# Jlink-OB.net
KiCad netlist of a schematic drawn in Altium Designer
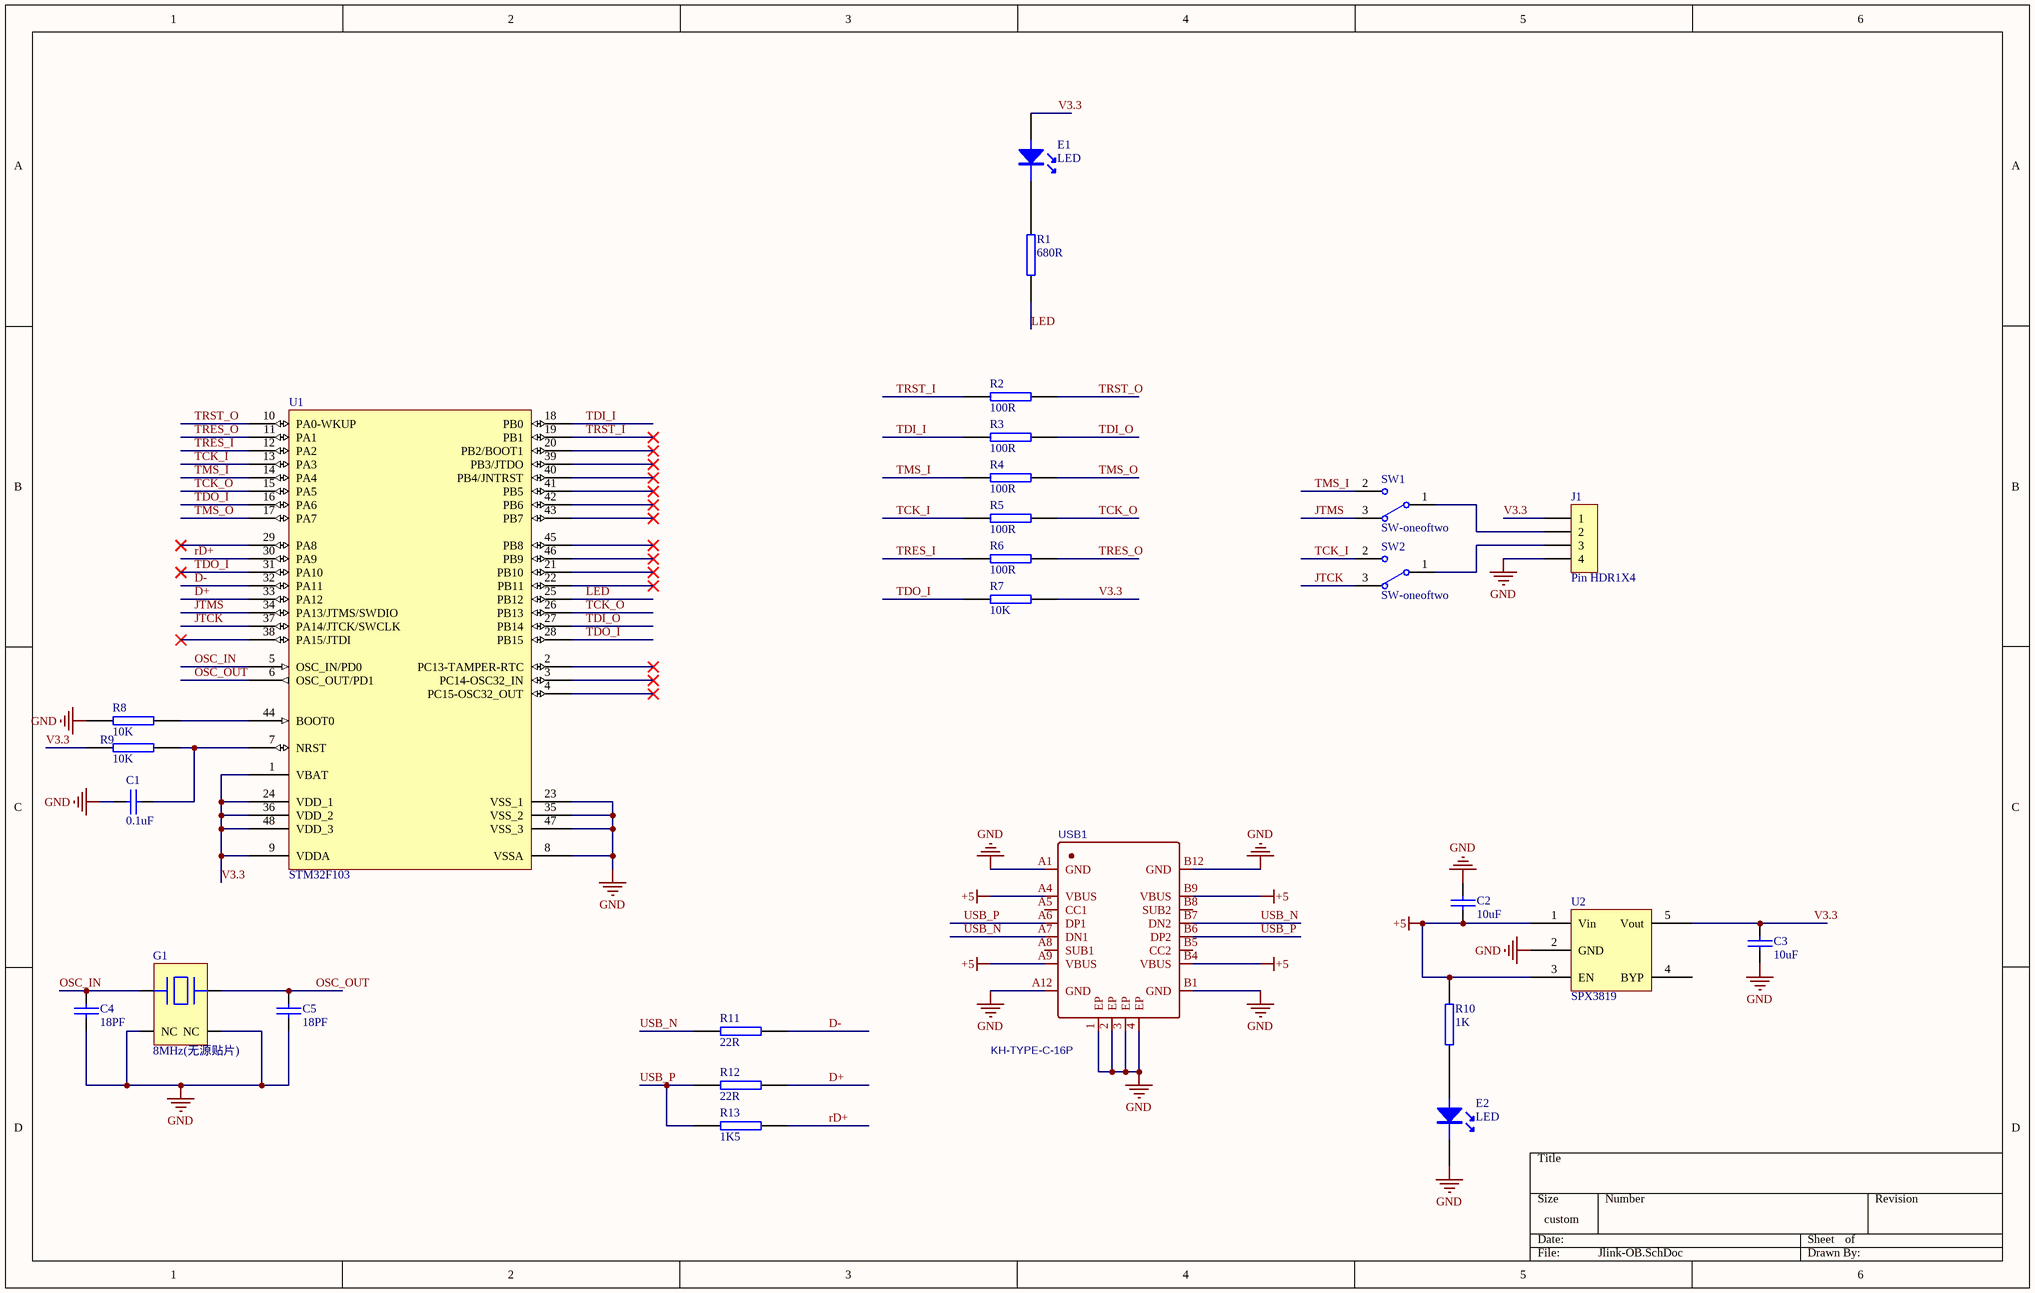
[diagram p0: Jlink-OB.SchDoc]

(export (version "E")
  (design (tool "Eeschema 10.0.6"))
  (components
    (comp (ref "C1")
      (value "0.1uF")
      (footprint "0603")
      (description "无极电容")
      (libsource (lib "chenjd") (part "CAP Nonpolarity"))
    )
    (comp (ref "C2")
      (value "10uF")
      (footprint "0603")
      (description "无极电容")
      (libsource (lib "chenjd") (part "CAP Nonpolarity"))
    )
    (comp (ref "C3")
      (value "10uF")
      (footprint "0603")
      (description "无极电容")
      (libsource (lib "chenjd") (part "CAP Nonpolarity"))
    )
    (comp (ref "C4")
      (value "18PF")
      (footprint "0603")
      (description "无极电容")
      (libsource (lib "chenjd") (part "CAP Nonpolarity"))
    )
    (comp (ref "C5")
      (value "18PF")
      (footprint "0603")
      (description "无极电容")
      (libsource (lib "chenjd") (part "CAP Nonpolarity"))
    )
    (comp (ref "E1")
      (value "LED")
      (footprint "LED_0603L")
      (description "LED灯")
      (libsource (lib "chenjd") (part "LED"))
    )
    (comp (ref "E2")
      (value "LED")
      (footprint "LED_0603L")
      (description "LED灯")
      (libsource (lib "chenjd") (part "LED"))
    )
    (comp (ref "G1")
      (value "8MHz(无源贴片)")
      (footprint "G3225")
      (description "无源晶振MCU使用")
      (libsource (lib "chenjd") (part "MM-11B"))
    )
    (comp (ref "J1")
      (value "Pin HDR1X4")
      (footprint "Pin HDR1X4/2.54mm-S")
      (libsource (lib "排针") (part "Pin HDR1X4"))
    )
    (comp (ref "R1")
      (value "680R")
      (footprint "0603")
      (description "电阻")
      (libsource (lib "chenjd") (part "R"))
    )
    (comp (ref "R2")
      (value "100R")
      (footprint "0603")
      (description "电阻")
      (libsource (lib "chenjd") (part "R"))
    )
    (comp (ref "R3")
      (value "100R")
      (footprint "0603")
      (description "电阻")
      (libsource (lib "chenjd") (part "R"))
    )
    (comp (ref "R4")
      (value "100R")
      (footprint "0603")
      (description "电阻")
      (libsource (lib "chenjd") (part "R"))
    )
    (comp (ref "R5")
      (value "100R")
      (footprint "0603")
      (description "电阻")
      (libsource (lib "chenjd") (part "R"))
    )
    (comp (ref "R6")
      (value "100R")
      (footprint "0603")
      (description "电阻")
      (libsource (lib "chenjd") (part "R"))
    )
    (comp (ref "R7")
      (value "10K")
      (footprint "0603")
      (description "电阻")
      (libsource (lib "chenjd") (part "R"))
    )
    (comp (ref "R8")
      (value "10K")
      (footprint "0603")
      (description "电阻")
      (libsource (lib "chenjd") (part "R"))
    )
    (comp (ref "R9")
      (value "10K")
      (footprint "0603")
      (description "电阻")
      (libsource (lib "chenjd") (part "R"))
    )
    (comp (ref "R10")
      (value "1K")
      (footprint "0603")
      (description "电阻")
      (libsource (lib "chenjd") (part "R"))
    )
    (comp (ref "R11")
      (value "22R")
      (footprint "0603")
      (description "电阻")
      (libsource (lib "chenjd") (part "R"))
    )
    (comp (ref "R12")
      (value "22R")
      (footprint "0603")
      (description "电阻")
      (libsource (lib "chenjd") (part "R"))
    )
    (comp (ref "R13")
      (value "1K5")
      (footprint "0603")
      (description "电阻")
      (libsource (lib "chenjd") (part "R"))
    )
    (comp (ref "SW1")
      (value "SW-oneoftwo")
      (footprint "SW-oneoftwo-0603")
      (description "二选一电阻开关")
      (libsource (lib "chenjd") (part "SW-oneoftwo"))
    )
    (comp (ref "SW2")
      (value "SW-oneoftwo")
      (footprint "SW-oneoftwo-0603")
      (description "二选一电阻开关")
      (libsource (lib "chenjd") (part "SW-oneoftwo"))
    )
    (comp (ref "U1")
      (value "STM32F103")
      (footprint "LQFP-48")
      (description "STM32F103C8T6")
      (fields (field (name "PUBLISHER") "Altium Limited"))
      (libsource (lib "chenjd") (part "STM32F103"))
    )
    (comp (ref "U2")
      (value "SPX3819")
      (footprint "SOT-23-5")
      (description "稳压器")
      (libsource (lib "chenjd") (part "SPX3819"))
    )
    (comp (ref "USB1")
      (value "KH-TYPE-C-16P")
      (footprint "USB-C-16P")
      (fields (field (name "BOM_SUPPLIER PART") "C709357") (field (name "CONTRIBUTOR") "LCSC"))
      (libsource (lib "chenjd") (part "USB-TYPE-C 16P"))
    )
  )
  (nets
    (net (code "1") (name "+5") (class "Default")
      (node (ref "C2") (pin "2") (pinfunction "2_2") (pintype "passive"))
      (node (ref "R10") (pin "1") (pinfunction "1_1") (pintype "passive"))
      (node (ref "U2") (pin "1") (pinfunction "Vin_1") (pintype "passive"))
      (node (ref "U2") (pin "3") (pinfunction "EN_3") (pintype "passive"))
      (node (ref "USB1") (pin "A4") (pinfunction "VBUS_A4") (pintype "passive"))
      (node (ref "USB1") (pin "A9") (pinfunction "VBUS_A9") (pintype "passive"))
      (node (ref "USB1") (pin "B4") (pinfunction "VBUS_B4") (pintype "passive"))
      (node (ref "USB1") (pin "B9") (pinfunction "VBUS_B9") (pintype "passive"))
    )
    (net (code "2") (name "/D+") (class "Default")
      (node (ref "R12") (pin "1") (pinfunction "1_1") (pintype "passive"))
      (node (ref "U1") (pin "33") (pinfunction "PA12_33") (pintype "bidirectional"))
    )
    (net (code "3") (name "/D-") (class "Default")
      (node (ref "R11") (pin "1") (pinfunction "1_1") (pintype "passive"))
      (node (ref "U1") (pin "32") (pinfunction "PA11_32") (pintype "bidirectional"))
    )
    (net (code "4") (name "/JTCK") (class "Default")
      (node (ref "SW2") (pin "3") (pinfunction "3_3") (pintype "passive"))
      (node (ref "U1") (pin "37") (pinfunction "PA14/JTCK/SWCLK_37") (pintype "bidirectional"))
    )
    (net (code "5") (name "/JTMS") (class "Default")
      (node (ref "SW1") (pin "3") (pinfunction "3_3") (pintype "passive"))
      (node (ref "U1") (pin "34") (pinfunction "PA13/JTMS/SWDIO_34") (pintype "bidirectional"))
    )
    (net (code "6") (name "/LED") (class "Default")
      (node (ref "R1") (pin "1") (pinfunction "1_1") (pintype "passive"))
      (node (ref "U1") (pin "25") (pinfunction "PB12_25") (pintype "bidirectional"))
    )
    (net (code "7") (name "/OSC_IN") (class "Default")
      (node (ref "C4") (pin "1") (pinfunction "1_1") (pintype "passive"))
      (node (ref "G1") (pin "1") (pinfunction "1_1") (pintype "passive"))
      (node (ref "U1") (pin "5") (pinfunction "OSC_IN/PD0_5") (pintype "input"))
    )
    (net (code "8") (name "/OSC_OUT") (class "Default")
      (node (ref "C5") (pin "1") (pinfunction "1_1") (pintype "passive"))
      (node (ref "G1") (pin "3") (pinfunction "3_3") (pintype "passive"))
      (node (ref "U1") (pin "6") (pinfunction "OSC_OUT/PD1_6") (pintype "output"))
    )
    (net (code "9") (name "/TCK_I") (class "Default")
      (node (ref "R5") (pin "2") (pinfunction "2_2") (pintype "passive"))
      (node (ref "SW2") (pin "2") (pinfunction "2_2") (pintype "passive"))
      (node (ref "U1") (pin "13") (pinfunction "PA3_13") (pintype "bidirectional"))
    )
    (net (code "10") (name "/TCK_O") (class "Default")
      (node (ref "R5") (pin "1") (pinfunction "1_1") (pintype "passive"))
      (node (ref "U1") (pin "15") (pinfunction "PA5_15") (pintype "bidirectional"))
      (node (ref "U1") (pin "26") (pinfunction "PB13_26") (pintype "bidirectional"))
    )
    (net (code "11") (name "/TDI_I") (class "Default")
      (node (ref "R3") (pin "2") (pinfunction "2_2") (pintype "passive"))
      (node (ref "U1") (pin "18") (pinfunction "PB0_18") (pintype "bidirectional"))
    )
    (net (code "12") (name "/TDI_O") (class "Default")
      (node (ref "R3") (pin "1") (pinfunction "1_1") (pintype "passive"))
      (node (ref "U1") (pin "27") (pinfunction "PB14_27") (pintype "bidirectional"))
    )
    (net (code "13") (name "/TDO_I") (class "Default")
      (node (ref "R7") (pin "2") (pinfunction "2_2") (pintype "passive"))
      (node (ref "U1") (pin "16") (pinfunction "PA6_16") (pintype "bidirectional"))
      (node (ref "U1") (pin "28") (pinfunction "PB15_28") (pintype "bidirectional"))
      (node (ref "U1") (pin "31") (pinfunction "PA10_31") (pintype "bidirectional"))
    )
    (net (code "14") (name "/TMS_I") (class "Default")
      (node (ref "R4") (pin "2") (pinfunction "2_2") (pintype "passive"))
      (node (ref "SW1") (pin "2") (pinfunction "2_2") (pintype "passive"))
      (node (ref "U1") (pin "14") (pinfunction "PA4_14") (pintype "bidirectional"))
    )
    (net (code "15") (name "/TMS_O") (class "Default")
      (node (ref "R4") (pin "1") (pinfunction "1_1") (pintype "passive"))
      (node (ref "U1") (pin "17") (pinfunction "PA7_17") (pintype "bidirectional"))
    )
    (net (code "16") (name "/TRES_I") (class "Default")
      (node (ref "R6") (pin "2") (pinfunction "2_2") (pintype "passive"))
      (node (ref "U1") (pin "12") (pinfunction "PA2_12") (pintype "bidirectional"))
    )
    (net (code "17") (name "/TRES_O") (class "Default")
      (node (ref "R6") (pin "1") (pinfunction "1_1") (pintype "passive"))
      (node (ref "U1") (pin "11") (pinfunction "PA1_11") (pintype "bidirectional"))
    )
    (net (code "18") (name "/TRST_I") (class "Default")
      (node (ref "R2") (pin "2") (pinfunction "2_2") (pintype "passive"))
      (node (ref "U1") (pin "19") (pinfunction "PB1_19") (pintype "bidirectional"))
    )
    (net (code "19") (name "/TRST_O") (class "Default")
      (node (ref "R2") (pin "1") (pinfunction "1_1") (pintype "passive"))
      (node (ref "U1") (pin "10") (pinfunction "PA0-WKUP_10") (pintype "bidirectional"))
    )
    (net (code "20") (name "/USB_N") (class "Default")
      (node (ref "R11") (pin "2") (pinfunction "2_2") (pintype "passive"))
      (node (ref "USB1") (pin "A7") (pinfunction "DN1_A7") (pintype "passive"))
      (node (ref "USB1") (pin "B7") (pinfunction "DN2_B7") (pintype "passive"))
    )
    (net (code "21") (name "/USB_P") (class "Default")
      (node (ref "R12") (pin "2") (pinfunction "2_2") (pintype "passive"))
      (node (ref "R13") (pin "2") (pinfunction "2_2") (pintype "passive"))
      (node (ref "USB1") (pin "A6") (pinfunction "DP1_A6") (pintype "passive"))
      (node (ref "USB1") (pin "B6") (pinfunction "DP2_B6") (pintype "passive"))
    )
    (net (code "22") (name "/V3.3") (class "Default")
      (node (ref "C3") (pin "1") (pinfunction "1_1") (pintype "passive"))
      (node (ref "E1") (pin "1") (pinfunction "1_1") (pintype "passive"))
      (node (ref "J1") (pin "1") (pinfunction "1_1") (pintype "passive"))
      (node (ref "R7") (pin "1") (pinfunction "1_1") (pintype "passive"))
      (node (ref "R9") (pin "1") (pinfunction "1_1") (pintype "passive"))
      (node (ref "U1") (pin "1") (pinfunction "VBAT_1") (pintype "power_in"))
      (node (ref "U1") (pin "24") (pinfunction "VDD_1_24") (pintype "power_in"))
      (node (ref "U1") (pin "36") (pinfunction "VDD_2_36") (pintype "power_in"))
      (node (ref "U1") (pin "48") (pinfunction "VDD_3_48") (pintype "power_in"))
      (node (ref "U1") (pin "9") (pinfunction "VDDA_9") (pintype "power_in"))
      (node (ref "U2") (pin "5") (pinfunction "Vout_5") (pintype "passive"))
    )
    (net (code "23") (name "/rD+") (class "Default")
      (node (ref "R13") (pin "1") (pinfunction "1_1") (pintype "passive"))
      (node (ref "U1") (pin "30") (pinfunction "PA9_30") (pintype "bidirectional"))
    )
    (net (code "24") (name "GND") (class "Default")
      (node (ref "C1") (pin "1") (pinfunction "1_1") (pintype "passive"))
      (node (ref "C2") (pin "1") (pinfunction "1_1") (pintype "passive"))
      (node (ref "C3") (pin "2") (pinfunction "2_2") (pintype "passive"))
      (node (ref "C4") (pin "2") (pinfunction "2_2") (pintype "passive"))
      (node (ref "C5") (pin "2") (pinfunction "2_2") (pintype "passive"))
      (node (ref "E2") (pin "2") (pinfunction "2_2") (pintype "passive"))
      (node (ref "G1") (pin "2") (pinfunction "NC_2") (pintype "passive"))
      (node (ref "G1") (pin "4") (pinfunction "NC_4") (pintype "passive"))
      (node (ref "J1") (pin "4") (pinfunction "4_4") (pintype "passive"))
      (node (ref "R8") (pin "1") (pinfunction "1_1") (pintype "passive"))
      (node (ref "U1") (pin "23") (pinfunction "VSS_1_23") (pintype "power_in"))
      (node (ref "U1") (pin "35") (pinfunction "VSS_2_35") (pintype "power_in"))
      (node (ref "U1") (pin "47") (pinfunction "VSS_3_47") (pintype "power_in"))
      (node (ref "U1") (pin "8") (pinfunction "VSSA_8") (pintype "power_in"))
      (node (ref "U2") (pin "2") (pinfunction "GND_2") (pintype "passive"))
      (node (ref "USB1") (pin "1") (pinfunction "EP_1") (pintype "passive"))
      (node (ref "USB1") (pin "2") (pinfunction "EP_2") (pintype "passive"))
      (node (ref "USB1") (pin "3") (pinfunction "EP_3") (pintype "passive"))
      (node (ref "USB1") (pin "4") (pinfunction "EP_4") (pintype "passive"))
      (node (ref "USB1") (pin "A1") (pinfunction "GND_A1") (pintype "passive"))
      (node (ref "USB1") (pin "A12") (pinfunction "GND_A12") (pintype "passive"))
      (node (ref "USB1") (pin "B1") (pinfunction "GND_B1") (pintype "passive"))
      (node (ref "USB1") (pin "B12") (pinfunction "GND_B12") (pintype "passive"))
    )
    (net (code "25") (name "Net-(E1-Pad2)") (class "Default")
      (node (ref "E1") (pin "2") (pinfunction "2_2") (pintype "passive"))
      (node (ref "R1") (pin "2") (pinfunction "2_2") (pintype "passive"))
    )
    (net (code "26") (name "Net-(E2-Pad1)") (class "Default")
      (node (ref "E2") (pin "1") (pinfunction "1_1") (pintype "passive"))
      (node (ref "R10") (pin "2") (pinfunction "2_2") (pintype "passive"))
    )
    (net (code "27") (name "Net-(J1-Pad2)") (class "Default")
      (node (ref "J1") (pin "2") (pinfunction "2_2") (pintype "passive"))
      (node (ref "SW1") (pin "1") (pinfunction "1_1") (pintype "passive"))
    )
    (net (code "28") (name "Net-(J1-Pad3)") (class "Default")
      (node (ref "J1") (pin "3") (pinfunction "3_3") (pintype "passive"))
      (node (ref "SW2") (pin "1") (pinfunction "1_1") (pintype "passive"))
    )
    (net (code "29") (name "Net-(U1-BOOT0)") (class "Default")
      (node (ref "R8") (pin "2") (pinfunction "2_2") (pintype "passive"))
      (node (ref "U1") (pin "44") (pinfunction "BOOT0_44") (pintype "input"))
    )
    (net (code "30") (name "Net-(U1-NRST)") (class "Default")
      (node (ref "C1") (pin "2") (pinfunction "2_2") (pintype "passive"))
      (node (ref "R9") (pin "2") (pinfunction "2_2") (pintype "passive"))
      (node (ref "U1") (pin "7") (pinfunction "NRST_7") (pintype "bidirectional"))
    )
    (net (code "31") (name "unconnected-(U1-PA8-Pad29)") (class "Default")
      (node (ref "U1") (pin "29") (pinfunction "PA8_29") (pintype "bidirectional+no_connect"))
    )
    (net (code "32") (name "unconnected-(U1-PA15{slash}JTDI-Pad38)") (class "Default")
      (node (ref "U1") (pin "38") (pinfunction "PA15/JTDI_38") (pintype "bidirectional+no_connect"))
    )
    (net (code "33") (name "unconnected-(U1-PB2{slash}BOOT1-Pad20)") (class "Default")
      (node (ref "U1") (pin "20") (pinfunction "PB2/BOOT1_20") (pintype "bidirectional+no_connect"))
    )
    (net (code "34") (name "unconnected-(U1-PB3{slash}JTDO-Pad39)") (class "Default")
      (node (ref "U1") (pin "39") (pinfunction "PB3/JTDO_39") (pintype "bidirectional+no_connect"))
    )
    (net (code "35") (name "unconnected-(U1-PB4{slash}JNTRST-Pad40)") (class "Default")
      (node (ref "U1") (pin "40") (pinfunction "PB4/JNTRST_40") (pintype "bidirectional+no_connect"))
    )
    (net (code "36") (name "unconnected-(U1-PB5-Pad41)") (class "Default")
      (node (ref "U1") (pin "41") (pinfunction "PB5_41") (pintype "bidirectional+no_connect"))
    )
    (net (code "37") (name "unconnected-(U1-PB6-Pad42)") (class "Default")
      (node (ref "U1") (pin "42") (pinfunction "PB6_42") (pintype "bidirectional+no_connect"))
    )
    (net (code "38") (name "unconnected-(U1-PB7-Pad43)") (class "Default")
      (node (ref "U1") (pin "43") (pinfunction "PB7_43") (pintype "bidirectional+no_connect"))
    )
    (net (code "39") (name "unconnected-(U1-PB8-Pad45)") (class "Default")
      (node (ref "U1") (pin "45") (pinfunction "PB8_45") (pintype "bidirectional+no_connect"))
    )
    (net (code "40") (name "unconnected-(U1-PB9-Pad46)") (class "Default")
      (node (ref "U1") (pin "46") (pinfunction "PB9_46") (pintype "bidirectional+no_connect"))
    )
    (net (code "41") (name "unconnected-(U1-PB10-Pad21)") (class "Default")
      (node (ref "U1") (pin "21") (pinfunction "PB10_21") (pintype "bidirectional+no_connect"))
    )
    (net (code "42") (name "unconnected-(U1-PB11-Pad22)") (class "Default")
      (node (ref "U1") (pin "22") (pinfunction "PB11_22") (pintype "bidirectional+no_connect"))
    )
    (net (code "43") (name "unconnected-(U1-PC13-TAMPER-RTC-Pad2)") (class "Default")
      (node (ref "U1") (pin "2") (pinfunction "PC13-TAMPER-RTC_2") (pintype "bidirectional+no_connect"))
    )
    (net (code "44") (name "unconnected-(U1-PC14-OSC32_IN-Pad3)") (class "Default")
      (node (ref "U1") (pin "3") (pinfunction "PC14-OSC32_IN_3") (pintype "bidirectional+no_connect"))
    )
    (net (code "45") (name "unconnected-(U1-PC15-OSC32_OUT-Pad4)") (class "Default")
      (node (ref "U1") (pin "4") (pinfunction "PC15-OSC32_OUT_4") (pintype "bidirectional+no_connect"))
    )
    (net (code "46") (name "unconnected-(U2-BYP-Pad4)") (class "Default")
      (node (ref "U2") (pin "4") (pinfunction "BYP_4") (pintype "passive"))
    )
    (net (code "47") (name "unconnected-(USB1-CC1-PadA5)") (class "Default")
      (node (ref "USB1") (pin "A5") (pinfunction "CC1_A5") (pintype "passive"))
    )
    (net (code "48") (name "unconnected-(USB1-CC2-PadB5)") (class "Default")
      (node (ref "USB1") (pin "B5") (pinfunction "CC2_B5") (pintype "passive"))
    )
    (net (code "49") (name "unconnected-(USB1-SUB1-PadA8)") (class "Default")
      (node (ref "USB1") (pin "A8") (pinfunction "SUB1_A8") (pintype "passive"))
    )
    (net (code "50") (name "unconnected-(USB1-SUB2-PadB8)") (class "Default")
      (node (ref "USB1") (pin "B8") (pinfunction "SUB2_B8") (pintype "passive"))
    )
  )
)
